# Buck_converter.net
KiCad netlist of a schematic drawn in Altium Designer
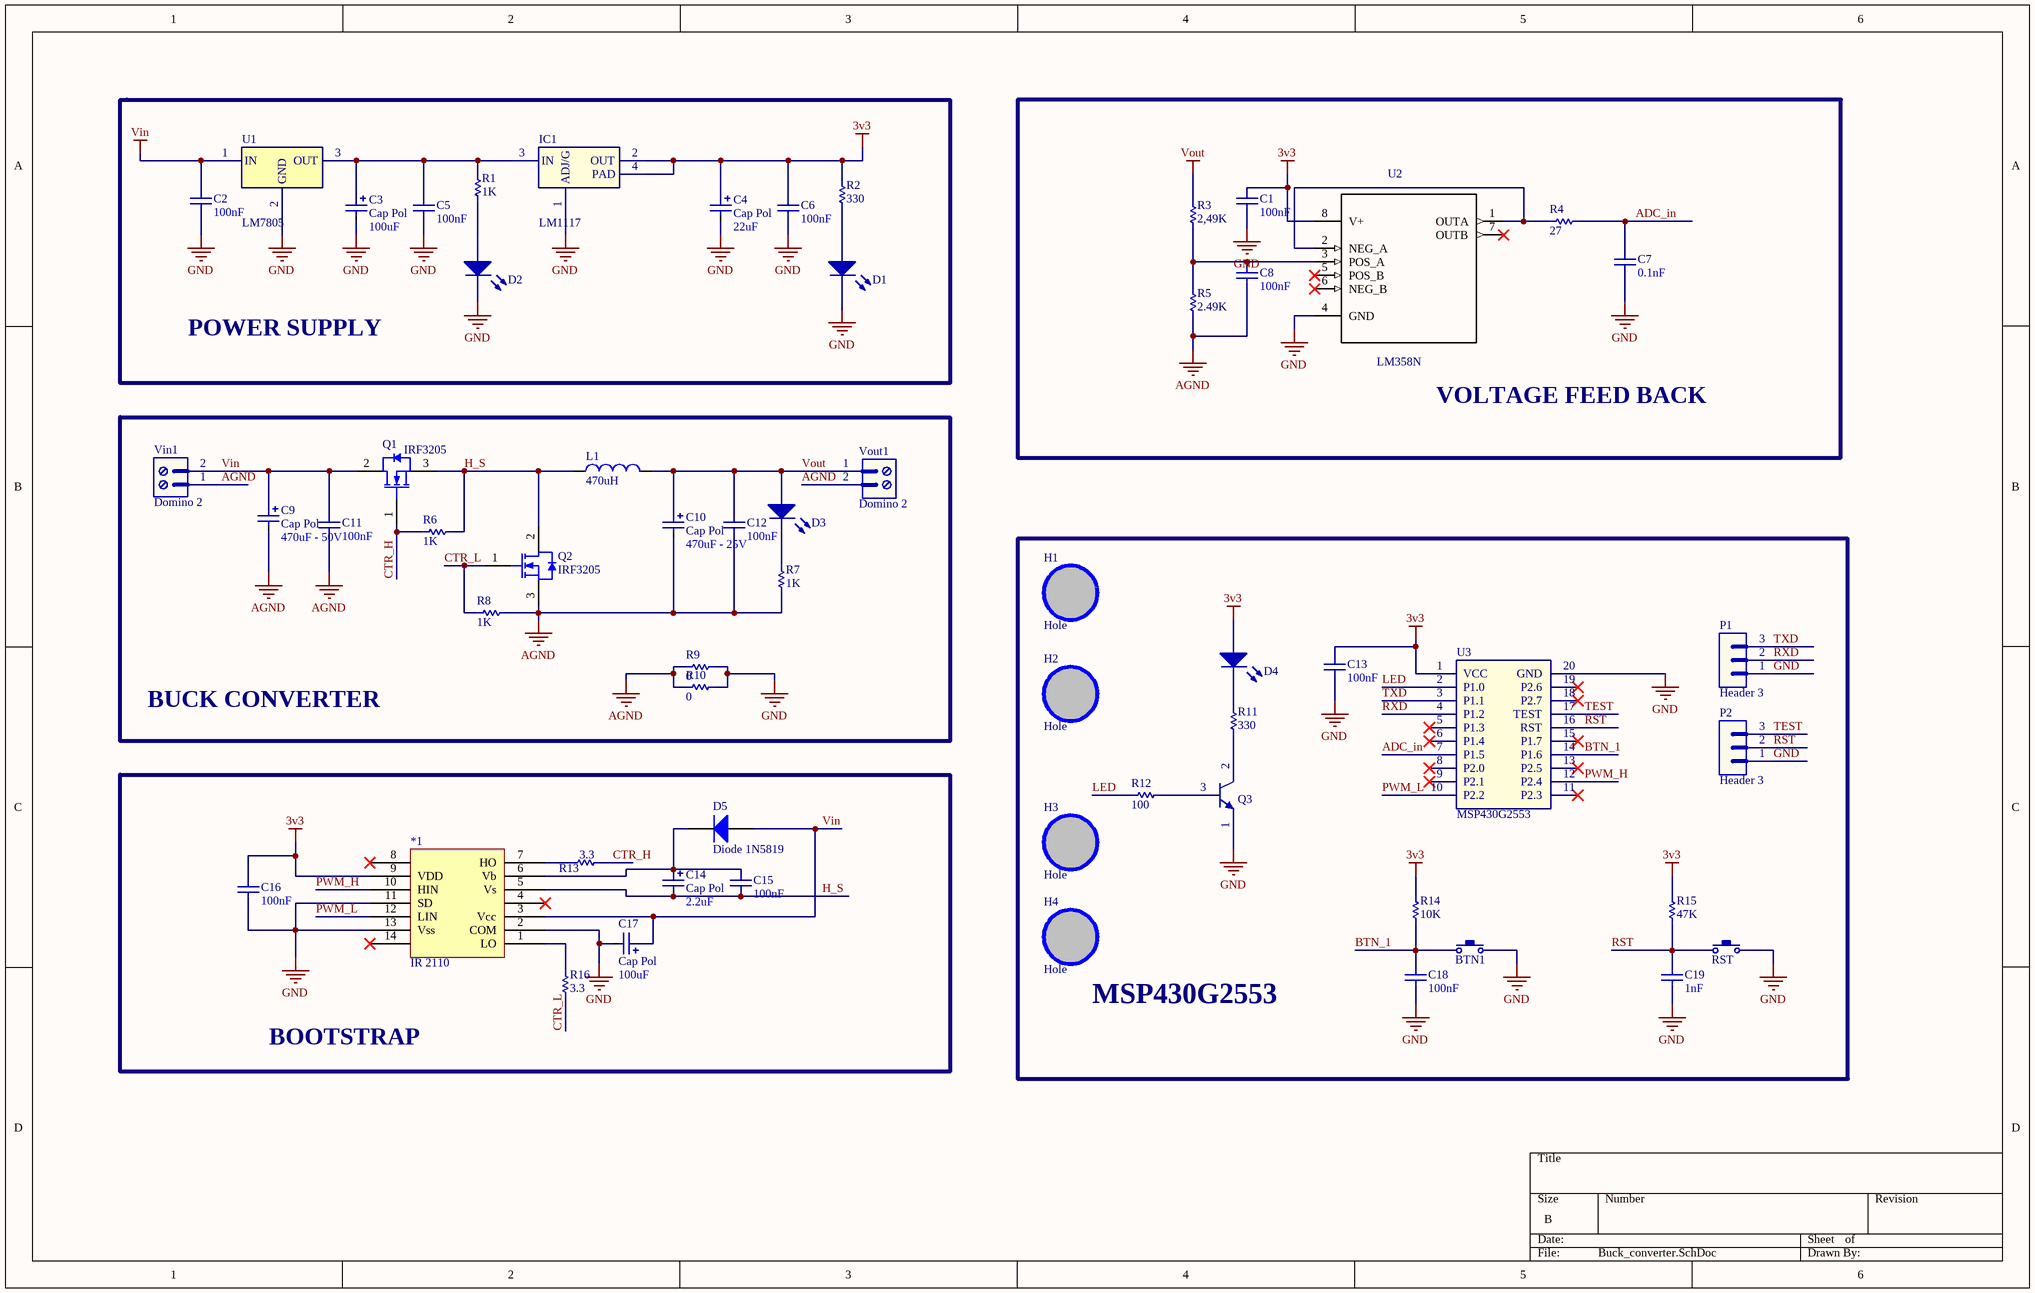
[diagram p0: Buck_converter.SchDoc]

(export (version "E")
  (design (tool "Eeschema 10.0.6"))
  (components
    (comp (ref "*1")
      (value "IR 2110")
      (footprint "IR 2110 DIP14")
      (libsource (lib "IR_2110") (part "IR 2110"))
    )
    (comp (ref "BTN1")
      (value "Button")
      (footprint "Button")
      (libsource (lib "PIF_C16_2_lib") (part "Button"))
    )
    (comp (ref "C1")
      (value "100nF")
      (footprint "CAP-SM-0805")
      (description "Capacitor")
      (fields (field (name "Comment") "Cap Non-Pol SMD"))
      (libsource (lib "PIF_C16_2_lib") (part "Cap Non-Pol SMD"))
    )
    (comp (ref "C2")
      (value "100nF")
      (footprint "CAP-SM-0805")
      (description "Capacitor")
      (fields (field (name "Comment") "Cap Non-Pol SMD"))
      (libsource (lib "PIF_C16_2_lib") (part "Cap Non-Pol SMD"))
    )
    (comp (ref "C3")
      (value "Cap Pol")
      (footprint "CP1/2")
      (description "Polarized Capacitor (Radial)")
      (fields (field (name "ALTIUM_VALUE") "100uF"))
      (libsource (lib "PIF_C16_2_lib") (part "Cap Pol"))
    )
    (comp (ref "C4")
      (value "Cap Pol")
      (footprint "CP1/2")
      (description "Polarized Capacitor (Radial)")
      (fields (field (name "ALTIUM_VALUE") "22uF"))
      (libsource (lib "PIF_C16_2_lib") (part "Cap Pol"))
    )
    (comp (ref "C5")
      (value "100nF")
      (footprint "CAP-SM-0805")
      (description "Capacitor")
      (fields (field (name "Comment") "Cap Non-Pol SMD"))
      (libsource (lib "PIF_C16_2_lib") (part "Cap Non-Pol SMD"))
    )
    (comp (ref "C6")
      (value "100nF")
      (footprint "CAP-SM-0805")
      (description "Capacitor")
      (fields (field (name "Comment") "Cap Non-Pol SMD"))
      (libsource (lib "PIF_C16_2_lib") (part "Cap Non-Pol SMD"))
    )
    (comp (ref "C7")
      (value "0.1nF")
      (footprint "CAP-SM-0805")
      (description "Capacitor")
      (fields (field (name "Comment") "Cap Non-Pol SMD"))
      (libsource (lib "PIF_C16_2_lib") (part "Cap Non-Pol SMD"))
    )
    (comp (ref "C8")
      (value "100nF")
      (footprint "CAP-SM-0805")
      (description "Capacitor")
      (fields (field (name "Comment") "Cap Non-Pol SMD"))
      (libsource (lib "PIF_C16_2_lib") (part "Cap Non-Pol SMD"))
    )
    (comp (ref "C9")
      (value "Cap Pol")
      (footprint "CP3/7")
      (description "Polarized Capacitor (Radial)")
      (fields (field (name "ALTIUM_VALUE") "470uF - 50V"))
      (libsource (lib "PIF_C16_2_lib") (part "Cap Pol"))
    )
    (comp (ref "C10")
      (value "Cap Pol")
      (footprint "CP1.5/3.4")
      (description "Polarized Capacitor (Radial)")
      (fields (field (name "ALTIUM_VALUE") "470uF - 25V"))
      (libsource (lib "PIF_C16_2_lib") (part "Cap Pol"))
    )
    (comp (ref "C11")
      (value "100nF")
      (footprint "CN1")
      (description "Capacitor")
      (fields (field (name "Comment") "Cap Non-Pol"))
      (libsource (lib "PIF_C16_2_lib") (part "Cap Non-Pol"))
    )
    (comp (ref "C12")
      (value "100nF")
      (footprint "CN1")
      (description "Capacitor")
      (fields (field (name "Comment") "Cap Non-Pol"))
      (libsource (lib "PIF_C16_2_lib") (part "Cap Non-Pol"))
    )
    (comp (ref "C13")
      (value "100nF")
      (footprint "CAP-SM-0805")
      (description "Capacitor")
      (fields (field (name "Comment") "Cap Non-Pol SMD"))
      (libsource (lib "PIF_C16_2_lib") (part "Cap Non-Pol SMD"))
    )
    (comp (ref "C14")
      (value "Cap Pol")
      (footprint "CP1/2")
      (description "Polarized Capacitor (Radial)")
      (fields (field (name "ALTIUM_VALUE") "2.2uF"))
      (libsource (lib "PIF_C16_2_lib") (part "Cap Pol"))
    )
    (comp (ref "C15")
      (value "100nF")
      (footprint "CN1")
      (description "Capacitor")
      (fields (field (name "Comment") "Cap Non-Pol"))
      (libsource (lib "PIF_C16_2_lib") (part "Cap Non-Pol"))
    )
    (comp (ref "C16")
      (value "100nF")
      (footprint "CAP-SM-0805")
      (description "Capacitor")
      (fields (field (name "Comment") "Cap Non-Pol SMD"))
      (libsource (lib "PIF_C16_2_lib") (part "Cap Non-Pol SMD"))
    )
    (comp (ref "C17")
      (value "Cap Pol")
      (footprint "CP1/2")
      (description "Polarized Capacitor (Radial)")
      (fields (field (name "ALTIUM_VALUE") "100uF"))
      (libsource (lib "PIF_C16_2_lib") (part "Cap Pol"))
    )
    (comp (ref "C18")
      (value "100nF")
      (footprint "CAP-SM-0805")
      (description "Capacitor")
      (fields (field (name "Comment") "Cap Non-Pol SMD"))
      (libsource (lib "PIF_C16_2_lib") (part "Cap Non-Pol SMD"))
    )
    (comp (ref "C19")
      (value "1nF")
      (footprint "CAP-SM-0805")
      (description "Capacitor")
      (fields (field (name "Comment") "Cap Non-Pol SMD"))
      (libsource (lib "PIF_C16_2_lib") (part "Cap Non-Pol SMD"))
    )
    (comp (ref "D1") (value "LED") (footprint "LED-3mm") (libsource (lib "PIF_C16_2_lib") (part "LED")))
    (comp (ref "D2") (value "LED") (footprint "LED-3mm") (libsource (lib "PIF_C16_2_lib") (part "LED")))
    (comp (ref "D3") (value "LED") (footprint "LED-3mm") (libsource (lib "PIF_C16_2_lib") (part "LED")))
    (comp (ref "D4") (value "LED") (footprint "LED-3mm") (libsource (lib "PIF_C16_2_lib") (part "LED")))
    (comp (ref "D5")
      (value "Diode 1N5819")
      (footprint "DO-41")
      (description "1 Amp General Purpose Rectifier")
      (fields (field (name "PUBLISHER") "Altium Limited"))
      (libsource (lib "Miscellaneous Devices") (part "Diode 1N4001"))
    )
    (comp (ref "H1")
      (value "Hole")
      (footprint "LO KHOAN 3MM")
      (description "Hole 3mm")
      (libsource (lib "PIF_C16_2_lib") (part "Hole"))
    )
    (comp (ref "H2")
      (value "Hole")
      (footprint "LO KHOAN 3MM")
      (description "Hole 3mm")
      (libsource (lib "PIF_C16_2_lib") (part "Hole"))
    )
    (comp (ref "H3")
      (value "Hole")
      (footprint "LO KHOAN 3MM")
      (description "Hole 3mm")
      (libsource (lib "PIF_C16_2_lib") (part "Hole"))
    )
    (comp (ref "H4")
      (value "Hole")
      (footprint "LO KHOAN 3MM")
      (description "Hole 3mm")
      (libsource (lib "PIF_C16_2_lib") (part "Hole"))
    )
    (comp (ref "IC1")
      (value "LM1117")
      (footprint "SOT223-4N")
      (description "Available in 1.8V, 2.5V, 2.85V, 3.3V, 5V, and  Adjustable Versions")
      (libsource (lib "PIF_C16_2_lib") (part "LM1117"))
    )
    (comp (ref "L1")
      (value "470uH")
      (footprint "INDUCTOR 12.5x12.5")
      (description "Inductor")
      (libsource (lib "PIF_Library") (part "Inductor"))
    )
    (comp (ref "P1")
      (value "Header 3")
      (footprint "JP3")
      (description "Header, 3-Pin")
      (fields (field (name "PUBLISHER") "Altium Limited"))
      (libsource (lib "PIF_C16_2_lib") (part "Header 3"))
    )
    (comp (ref "P2")
      (value "Header 3")
      (footprint "JP3")
      (description "Header, 3-Pin")
      (fields (field (name "PUBLISHER") "Altium Limited"))
      (libsource (lib "PIF_C16_2_lib") (part "Header 3"))
    )
    (comp (ref "Q1")
      (value "IRF3205")
      (footprint "INF-PG-TO220-3-1")
      (fields (field (name "MANUFACTURER") "Infineon") (field (name "PARTNUMBER") "IPP039N04L G"))
      (libsource (lib "Infineon_Power_MOSFET") (part "IPP039N04L G"))
    )
    (comp (ref "Q2")
      (value "IRF3205")
      (footprint "INF-PG-TO220-3-1")
      (fields (field (name "MANUFACTURER") "Infineon") (field (name "PARTNUMBER") "IPP039N04L G"))
      (libsource (lib "Infineon_Power_MOSFET") (part "IPP039N04L G"))
    )
    (comp (ref "Q3")
      (value "Transistor C1815")
      (footprint "SOT23-3 Leads")
      (libsource (lib "PIF_C16_2_lib") (part "C1815"))
    )
    (comp (ref "R1")
      (value "1K")
      (footprint "RES-SM-0805")
      (fields (field (name "Comment") "Resistor 1/4W"))
      (libsource (lib "PIF_C16_2_lib") (part "RES"))
    )
    (comp (ref "R2")
      (value "330")
      (footprint "RES-SM-0805")
      (fields (field (name "Comment") "Resistor 1/4W"))
      (libsource (lib "PIF_C16_2_lib") (part "RES"))
    )
    (comp (ref "R3")
      (value "2,49K")
      (footprint "RES-SM-0805")
      (fields (field (name "Comment") "Resistor 1/4W"))
      (libsource (lib "PIF_C16_2_lib") (part "RES"))
    )
    (comp (ref "R4")
      (value "27")
      (footprint "RES-SM-0805")
      (fields (field (name "Comment") "Resistor 1/4W"))
      (libsource (lib "PIF_C16_2_lib") (part "RES"))
    )
    (comp (ref "R5")
      (value "2.49K")
      (footprint "RES-SM-0805")
      (fields (field (name "Comment") "Resistor 1/4W"))
      (libsource (lib "PIF_C16_2_lib") (part "RES"))
    )
    (comp (ref "R6")
      (value "1K")
      (footprint "RES 1/2W")
      (fields (field (name "Comment") "Resistor 1/4W"))
      (libsource (lib "PIF_C16_2_lib") (part "RES"))
    )
    (comp (ref "R7")
      (value "1K")
      (footprint "RES-SM-0805")
      (fields (field (name "Comment") "Resistor 1/4W"))
      (libsource (lib "PIF_C16_2_lib") (part "RES"))
    )
    (comp (ref "R8")
      (value "1K")
      (footprint "RES-SM-0805")
      (fields (field (name "Comment") "Resistor 1/4W"))
      (libsource (lib "PIF_C16_2_lib") (part "RES"))
    )
    (comp (ref "R9")
      (value "0")
      (footprint "RES-SM-0805")
      (fields (field (name "Comment") "Resistor 1/4W"))
      (libsource (lib "PIF_C16_2_lib") (part "RES"))
    )
    (comp (ref "R10")
      (value "0")
      (footprint "RES-SM-0805")
      (fields (field (name "Comment") "Resistor 1/4W"))
      (libsource (lib "PIF_C16_2_lib") (part "RES"))
    )
    (comp (ref "R11")
      (value "330")
      (footprint "RES-SM-0805")
      (fields (field (name "Comment") "Resistor 1/4W"))
      (libsource (lib "PIF_C16_2_lib") (part "RES"))
    )
    (comp (ref "R12")
      (value "100")
      (footprint "RES-SM-0805")
      (fields (field (name "Comment") "Resistor 1/4W"))
      (libsource (lib "PIF_C16_2_lib") (part "RES"))
    )
    (comp (ref "R13")
      (value "3.3")
      (footprint "RES-SM-0805")
      (fields (field (name "Comment") "Resistor 1/4W"))
      (libsource (lib "PIF_C16_2_lib") (part "RES"))
    )
    (comp (ref "R14")
      (value "10K")
      (footprint "RES-SM-0805")
      (fields (field (name "Comment") "Resistor 1/4W"))
      (libsource (lib "PIF_C16_2_lib") (part "RES"))
    )
    (comp (ref "R15")
      (value "47K")
      (footprint "RES-SM-0805")
      (fields (field (name "Comment") "Resistor 1/4W"))
      (libsource (lib "PIF_C16_2_lib") (part "RES"))
    )
    (comp (ref "R16")
      (value "3.3")
      (footprint "RES-SM-0805")
      (fields (field (name "Comment") "Resistor 1/4W"))
      (libsource (lib "PIF_C16_2_lib") (part "RES"))
    )
    (comp (ref "RST") (value "Button") (footprint "Button") (libsource (lib "PIF_C16_2_lib") (part "Button")))
    (comp (ref "U1")
      (value "LM7805")
      (footprint "QTO-220")
      (description "Positive Voltage Regulator")
      (libsource (lib "PIF_C16_2_lib") (part "LM7805"))
    )
    (comp (ref "U2")
      (value "LM358N")
      (footprint "DIP254P762X508-8")
      (fields (field (name "MF") "STMicroelectronics"))
      (libsource (lib "LM358N") (part "LM358N"))
    )
    (comp (ref "U3")
      (value "MSP430G2553")
      (footprint "DIP20/W0.3")
      (description "IC MCU 16BIT 16KB FLASH")
      (libsource (lib "PIF_C16_2_lib") (part "MSP430G2553"))
    )
    (comp (ref "Vin1")
      (value "Domino 2")
      (footprint "DOMINO 2- 5mm")
      (description "Domino, 2-Pin")
      (fields (field (name "PUBLISHER") "Altium Limited"))
      (libsource (lib "") (part "Domino 2_1"))
    )
    (comp (ref "Vout1")
      (value "Domino 2")
      (footprint "DOMINO 2- 5mm")
      (description "Domino, 2-Pin")
      (fields (field (name "PUBLISHER") "Altium Limited"))
      (libsource (lib "PIF_C16_2_lib") (part "Domino 2"))
    )
  )
  (nets
    (net (code "1") (name "/ADC_in") (class "Default")
      (node (ref "C7") (pin "2") (pinfunction "2_2") (pintype "passive"))
      (node (ref "R4") (pin "2") (pintype "passive"))
      (node (ref "U3") (pin "7") (pinfunction "P1.5_7") (pintype "passive"))
    )
    (net (code "2") (name "/BTN_1") (class "Default")
      (node (ref "BTN1") (pin "1") (pintype "passive"))
      (node (ref "C18") (pin "1") (pinfunction "1_1") (pintype "passive"))
      (node (ref "R14") (pin "1") (pintype "passive"))
      (node (ref "U3") (pin "14") (pinfunction "P1.6_14") (pintype "passive"))
    )
    (net (code "3") (name "/CTR_H") (class "Default")
      (node (ref "Q1") (pin "1") (pinfunction "GATE_1") (pintype "passive"))
      (node (ref "R13") (pin "2") (pintype "passive"))
      (node (ref "R6") (pin "1") (pintype "passive"))
    )
    (net (code "4") (name "/CTR_L") (class "Default")
      (node (ref "Q2") (pin "1") (pinfunction "GATE_1") (pintype "passive"))
      (node (ref "R16") (pin "1") (pintype "passive"))
      (node (ref "R8") (pin "1") (pintype "passive"))
    )
    (net (code "5") (name "/H_S") (class "Default")
      (node (ref "*1") (pin "5") (pinfunction "Vs_5") (pintype "passive"))
      (node (ref "C14") (pin "2") (pinfunction "2_2") (pintype "passive"))
      (node (ref "C15") (pin "1") (pinfunction "1_1") (pintype "passive"))
      (node (ref "L1") (pin "1") (pinfunction "1_1") (pintype "passive"))
      (node (ref "Q1") (pin "3") (pinfunction "SOURCE_3") (pintype "passive"))
      (node (ref "Q2") (pin "2") (pinfunction "DRAIN_2") (pintype "passive"))
      (node (ref "R6") (pin "2") (pintype "passive"))
    )
    (net (code "6") (name "/LED") (class "Default")
      (node (ref "R12") (pin "1") (pintype "passive"))
      (node (ref "U3") (pin "2") (pinfunction "P1.0_2") (pintype "passive"))
    )
    (net (code "7") (name "/PWM_H") (class "Default")
      (node (ref "*1") (pin "10") (pinfunction "HIN_10") (pintype "passive"))
      (node (ref "U3") (pin "12") (pinfunction "P2.4_12") (pintype "passive"))
    )
    (net (code "8") (name "/PWM_L") (class "Default")
      (node (ref "*1") (pin "12") (pinfunction "LIN_12") (pintype "passive"))
      (node (ref "U3") (pin "10") (pinfunction "P2.2_10") (pintype "passive"))
    )
    (net (code "9") (name "/RST") (class "Default")
      (node (ref "C19") (pin "2") (pinfunction "2_2") (pintype "passive"))
      (node (ref "P2") (pin "2") (pinfunction "2_2") (pintype "passive"))
      (node (ref "R15") (pin "1") (pintype "passive"))
      (node (ref "RST") (pin "1") (pintype "passive"))
      (node (ref "U3") (pin "16") (pinfunction "RST_16") (pintype "passive"))
    )
    (net (code "10") (name "/RXD") (class "Default")
      (node (ref "P1") (pin "2") (pinfunction "2_2") (pintype "passive"))
      (node (ref "U3") (pin "4") (pinfunction "P1.2_4") (pintype "passive"))
    )
    (net (code "11") (name "/TEST") (class "Default")
      (node (ref "P2") (pin "3") (pinfunction "3_3") (pintype "passive"))
      (node (ref "U3") (pin "17") (pinfunction "TEST_17") (pintype "passive"))
    )
    (net (code "12") (name "/TXD") (class "Default")
      (node (ref "P1") (pin "3") (pinfunction "3_3") (pintype "passive"))
      (node (ref "U3") (pin "3") (pinfunction "P1.1_3") (pintype "passive"))
    )
    (net (code "13") (name "3v3") (class "Default")
      (node (ref "*1") (pin "9") (pinfunction "VDD_9") (pintype "passive"))
      (node (ref "C1") (pin "2") (pinfunction "2_2") (pintype "passive"))
      (node (ref "C13") (pin "2") (pinfunction "2_2") (pintype "passive"))
      (node (ref "C16") (pin "2") (pinfunction "2_2") (pintype "passive"))
      (node (ref "C4") (pin "1") (pinfunction "1_1") (pintype "passive"))
      (node (ref "C6") (pin "2") (pinfunction "2_2") (pintype "passive"))
      (node (ref "D4") (pin "1") (pinfunction "A_1") (pintype "passive"))
      (node (ref "IC1") (pin "2") (pinfunction "OUT_2") (pintype "passive"))
      (node (ref "IC1") (pin "4") (pinfunction "PAD_4") (pintype "passive"))
      (node (ref "R14") (pin "2") (pintype "passive"))
      (node (ref "R15") (pin "2") (pintype "passive"))
      (node (ref "R2") (pin "2") (pintype "passive"))
      (node (ref "U2") (pin "8") (pinfunction "V+_8") (pintype "power_in"))
      (node (ref "U3") (pin "1") (pinfunction "VCC_1") (pintype "power_in"))
    )
    (net (code "14") (name "AGND") (class "Default")
      (node (ref "C10") (pin "2") (pinfunction "2_2") (pintype "passive"))
      (node (ref "C11") (pin "1") (pinfunction "1_1") (pintype "passive"))
      (node (ref "C12") (pin "1") (pinfunction "1_1") (pintype "passive"))
      (node (ref "C8") (pin "1") (pinfunction "1_1") (pintype "passive"))
      (node (ref "C9") (pin "2") (pinfunction "2_2") (pintype "passive"))
      (node (ref "Q2") (pin "3") (pinfunction "SOURCE_3") (pintype "passive"))
      (node (ref "R10") (pin "1") (pintype "passive"))
      (node (ref "R5") (pin "1") (pintype "passive"))
      (node (ref "R7") (pin "1") (pintype "passive"))
      (node (ref "R8") (pin "2") (pintype "passive"))
      (node (ref "R9") (pin "1") (pintype "passive"))
      (node (ref "Vin1") (pin "1") (pinfunction "1_1") (pintype "passive"))
      (node (ref "Vout1") (pin "2") (pinfunction "2_2") (pintype "passive"))
    )
    (net (code "15") (name "GND") (class "Default")
      (node (ref "*1") (pin "11") (pinfunction "SD_11") (pintype "passive"))
      (node (ref "*1") (pin "13") (pinfunction "Vss_13") (pintype "passive"))
      (node (ref "*1") (pin "2") (pinfunction "COM_2") (pintype "passive"))
      (node (ref "BTN1") (pin "2") (pintype "passive"))
      (node (ref "C1") (pin "1") (pinfunction "1_1") (pintype "passive"))
      (node (ref "C13") (pin "1") (pinfunction "1_1") (pintype "passive"))
      (node (ref "C16") (pin "1") (pinfunction "1_1") (pintype "passive"))
      (node (ref "C17") (pin "2") (pinfunction "2_2") (pintype "passive"))
      (node (ref "C18") (pin "2") (pinfunction "2_2") (pintype "passive"))
      (node (ref "C19") (pin "1") (pinfunction "1_1") (pintype "passive"))
      (node (ref "C2") (pin "1") (pinfunction "1_1") (pintype "passive"))
      (node (ref "C3") (pin "2") (pinfunction "2_2") (pintype "passive"))
      (node (ref "C4") (pin "2") (pinfunction "2_2") (pintype "passive"))
      (node (ref "C5") (pin "1") (pinfunction "1_1") (pintype "passive"))
      (node (ref "C6") (pin "1") (pinfunction "1_1") (pintype "passive"))
      (node (ref "C7") (pin "1") (pinfunction "1_1") (pintype "passive"))
      (node (ref "D1") (pin "2") (pinfunction "K_2") (pintype "passive"))
      (node (ref "D2") (pin "2") (pinfunction "K_2") (pintype "passive"))
      (node (ref "IC1") (pin "1") (pinfunction "ADJ/G_1") (pintype "passive"))
      (node (ref "P1") (pin "1") (pinfunction "1_1") (pintype "passive"))
      (node (ref "P2") (pin "1") (pinfunction "1_1") (pintype "passive"))
      (node (ref "Q3") (pin "1") (pinfunction "E_1") (pintype "passive"))
      (node (ref "R10") (pin "2") (pintype "passive"))
      (node (ref "R9") (pin "2") (pintype "passive"))
      (node (ref "RST") (pin "2") (pintype "passive"))
      (node (ref "U1") (pin "2") (pinfunction "GND_2") (pintype "power_in"))
      (node (ref "U2") (pin "4") (pinfunction "GND_4") (pintype "passive"))
      (node (ref "U3") (pin "20") (pinfunction "GND_20") (pintype "power_in"))
    )
    (net (code "16") (name "Net-(*1-HO)") (class "Default")
      (node (ref "*1") (pin "7") (pinfunction "HO_7") (pintype "passive"))
      (node (ref "R13") (pin "1") (pintype "passive"))
    )
    (net (code "17") (name "Net-(*1-LO)") (class "Default")
      (node (ref "*1") (pin "1") (pinfunction "LO_1") (pintype "passive"))
      (node (ref "R16") (pin "2") (pintype "passive"))
    )
    (net (code "18") (name "Net-(*1-Vb)") (class "Default")
      (node (ref "*1") (pin "6") (pinfunction "Vb_6") (pintype "passive"))
      (node (ref "C14") (pin "1") (pinfunction "1_1") (pintype "passive"))
      (node (ref "C15") (pin "2") (pinfunction "2_2") (pintype "passive"))
      (node (ref "D5") (pin "2") (pinfunction "K_2") (pintype "passive"))
    )
    (net (code "19") (name "Net-(D1-A)") (class "Default")
      (node (ref "D1") (pin "1") (pinfunction "A_1") (pintype "passive"))
      (node (ref "R2") (pin "1") (pintype "passive"))
    )
    (net (code "20") (name "Net-(D2-A)") (class "Default")
      (node (ref "D2") (pin "1") (pinfunction "A_1") (pintype "passive"))
      (node (ref "R1") (pin "1") (pintype "passive"))
    )
    (net (code "21") (name "Net-(D3-K)") (class "Default")
      (node (ref "D3") (pin "2") (pinfunction "K_2") (pintype "passive"))
      (node (ref "R7") (pin "2") (pintype "passive"))
    )
    (net (code "22") (name "Net-(D4-K)") (class "Default")
      (node (ref "D4") (pin "2") (pinfunction "K_2") (pintype "passive"))
      (node (ref "R11") (pin "2") (pintype "passive"))
    )
    (net (code "23") (name "Net-(IC1-IN)") (class "Default")
      (node (ref "C3") (pin "1") (pinfunction "1_1") (pintype "passive"))
      (node (ref "C5") (pin "2") (pinfunction "2_2") (pintype "passive"))
      (node (ref "IC1") (pin "3") (pinfunction "IN_3") (pintype "passive"))
      (node (ref "R1") (pin "2") (pintype "passive"))
      (node (ref "U1") (pin "3") (pinfunction "OUT_3") (pintype "power_in"))
    )
    (net (code "24") (name "Net-(Q3-B)") (class "Default")
      (node (ref "Q3") (pin "3") (pinfunction "B_3") (pintype "passive"))
      (node (ref "R12") (pin "2") (pintype "passive"))
    )
    (net (code "25") (name "Net-(Q3-C)") (class "Default")
      (node (ref "Q3") (pin "2") (pinfunction "C_2") (pintype "passive"))
      (node (ref "R11") (pin "1") (pintype "passive"))
    )
    (net (code "26") (name "Net-(U2-NEG_A)") (class "Default")
      (node (ref "R4") (pin "1") (pintype "passive"))
      (node (ref "U2") (pin "1") (pinfunction "OUTA_1") (pintype "output"))
      (node (ref "U2") (pin "2") (pinfunction "NEG_A_2") (pintype "input"))
    )
    (net (code "27") (name "Net-(U2-POS_A)") (class "Default")
      (node (ref "C8") (pin "2") (pinfunction "2_2") (pintype "passive"))
      (node (ref "R3") (pin "1") (pintype "passive"))
      (node (ref "R5") (pin "2") (pintype "passive"))
      (node (ref "U2") (pin "3") (pinfunction "POS_A_3") (pintype "input"))
    )
    (net (code "28") (name "Vin") (class "Default")
      (node (ref "*1") (pin "3") (pinfunction "Vcc_3") (pintype "passive"))
      (node (ref "C11") (pin "2") (pinfunction "2_2") (pintype "passive"))
      (node (ref "C17") (pin "1") (pinfunction "1_1") (pintype "passive"))
      (node (ref "C2") (pin "2") (pinfunction "2_2") (pintype "passive"))
      (node (ref "C9") (pin "1") (pinfunction "1_1") (pintype "passive"))
      (node (ref "D5") (pin "1") (pinfunction "A_1") (pintype "passive"))
      (node (ref "Q1") (pin "2") (pinfunction "DRAIN_2") (pintype "passive"))
      (node (ref "U1") (pin "1") (pinfunction "IN_1") (pintype "power_in"))
      (node (ref "Vin1") (pin "2") (pinfunction "2_2") (pintype "passive"))
    )
    (net (code "29") (name "Vout") (class "Default")
      (node (ref "C10") (pin "1") (pinfunction "1_1") (pintype "passive"))
      (node (ref "C12") (pin "2") (pinfunction "2_2") (pintype "passive"))
      (node (ref "D3") (pin "1") (pinfunction "A_1") (pintype "passive"))
      (node (ref "L1") (pin "2") (pinfunction "2_2") (pintype "passive"))
      (node (ref "R3") (pin "2") (pintype "passive"))
      (node (ref "Vout1") (pin "1") (pinfunction "1_1") (pintype "passive"))
    )
    (net (code "30") (name "unconnected-(*1-Pad4)") (class "Default")
      (node (ref "*1") (pin "4") (pintype "passive+no_connect"))
    )
    (net (code "31") (name "unconnected-(*1-Pad8)") (class "Default")
      (node (ref "*1") (pin "8") (pintype "passive+no_connect"))
    )
    (net (code "32") (name "unconnected-(*1-Pad14)") (class "Default")
      (node (ref "*1") (pin "14") (pintype "passive+no_connect"))
    )
    (net (code "33") (name "unconnected-(H1-Pad1)") (class "Default")
      (node (ref "H1") (pin "1") (pinfunction "1_1") (pintype "passive"))
    )
    (net (code "34") (name "unconnected-(H2-Pad1)") (class "Default")
      (node (ref "H2") (pin "1") (pinfunction "1_1") (pintype "passive"))
    )
    (net (code "35") (name "unconnected-(H3-Pad1)") (class "Default")
      (node (ref "H3") (pin "1") (pinfunction "1_1") (pintype "passive"))
    )
    (net (code "36") (name "unconnected-(H4-Pad1)") (class "Default")
      (node (ref "H4") (pin "1") (pinfunction "1_1") (pintype "passive"))
    )
    (net (code "37") (name "unconnected-(U2-NEG_B-Pad6)") (class "Default")
      (node (ref "U2") (pin "6") (pinfunction "NEG_B_6") (pintype "input+no_connect"))
    )
    (net (code "38") (name "unconnected-(U2-OUTB-Pad7)") (class "Default")
      (node (ref "U2") (pin "7") (pinfunction "OUTB_7") (pintype "output+no_connect"))
    )
    (net (code "39") (name "unconnected-(U2-POS_B-Pad5)") (class "Default")
      (node (ref "U2") (pin "5") (pinfunction "POS_B_5") (pintype "input+no_connect"))
    )
    (net (code "40") (name "unconnected-(U3-P1.3-Pad5)") (class "Default")
      (node (ref "U3") (pin "5") (pinfunction "P1.3_5") (pintype "passive+no_connect"))
    )
    (net (code "41") (name "unconnected-(U3-P1.4-Pad6)") (class "Default")
      (node (ref "U3") (pin "6") (pinfunction "P1.4_6") (pintype "passive+no_connect"))
    )
    (net (code "42") (name "unconnected-(U3-P1.7-Pad15)") (class "Default")
      (node (ref "U3") (pin "15") (pinfunction "P1.7_15") (pintype "passive+no_connect"))
    )
    (net (code "43") (name "unconnected-(U3-P2.0-Pad8)") (class "Default")
      (node (ref "U3") (pin "8") (pinfunction "P2.0_8") (pintype "passive+no_connect"))
    )
    (net (code "44") (name "unconnected-(U3-P2.1-Pad9)") (class "Default")
      (node (ref "U3") (pin "9") (pinfunction "P2.1_9") (pintype "passive+no_connect"))
    )
    (net (code "45") (name "unconnected-(U3-P2.3-Pad11)") (class "Default")
      (node (ref "U3") (pin "11") (pinfunction "P2.3_11") (pintype "passive+no_connect"))
    )
    (net (code "46") (name "unconnected-(U3-P2.5-Pad13)") (class "Default")
      (node (ref "U3") (pin "13") (pinfunction "P2.5_13") (pintype "passive+no_connect"))
    )
    (net (code "47") (name "unconnected-(U3-P2.6-Pad19)") (class "Default")
      (node (ref "U3") (pin "19") (pinfunction "P2.6_19") (pintype "passive+no_connect"))
    )
    (net (code "48") (name "unconnected-(U3-P2.7-Pad18)") (class "Default")
      (node (ref "U3") (pin "18") (pinfunction "P2.7_18") (pintype "passive+no_connect"))
    )
  )
)
